# honda_type1.net
KiCad netlist of a schematic drawn in EAGLE
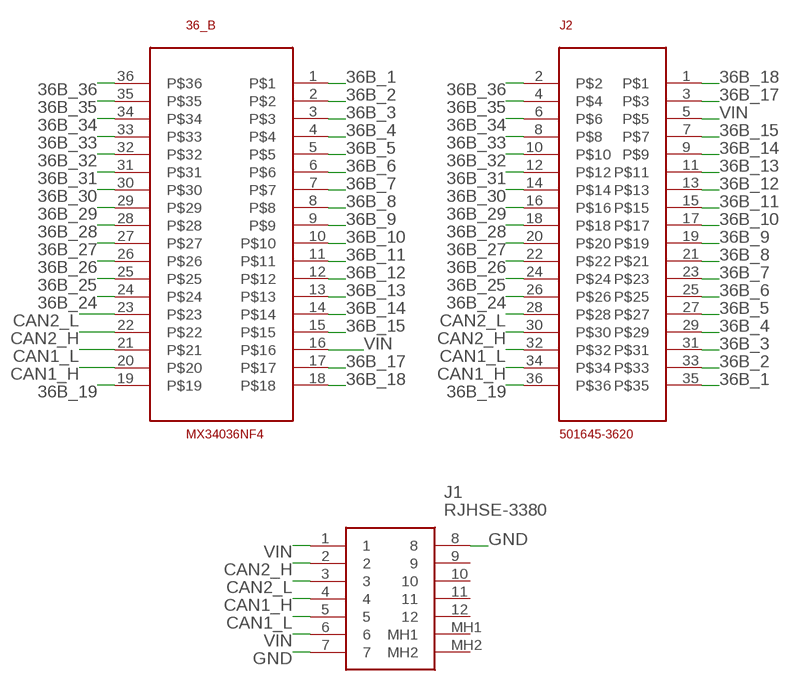
[diagram p0: schematic, sheet 1]

(export (version "E")
  (design (tool "Eeschema 10.0.6"))
  (components
    (comp (ref "36_B")
      (value "MX34036NF4")
      (footprint "eagle-import:MX34036NF2")
      (libsource (lib "eagle-import") (part "MX34036NF4"))
    )
    (comp (ref "J1")
      (value "RJHSE-3380")
      (footprint "eagle-import:RJHSE3384")
      (fields (field (name "MOUSER2_PART_NUMBER") "523-RJHSE-3380"))
      (libsource (lib "eagle-import") (part "RJHSE-3380"))
    )
    (comp (ref "J2")
      (value "501645-3620")
      (footprint "eagle-import:501645-3620")
      (libsource (lib "eagle-import") (part "501645-3620"))
    )
  )
  (nets
    (net (code "1") (name "36B_1") (class "Default")
      (node (ref "36_B") (pin "1") (pinfunction "P$1_1") (pintype "bidirectional"))
      (node (ref "J2") (pin "35") (pinfunction "P$35_35") (pintype "bidirectional"))
    )
    (net (code "2") (name "36B_2") (class "Default")
      (node (ref "36_B") (pin "2") (pinfunction "P$2_2") (pintype "bidirectional"))
      (node (ref "J2") (pin "33") (pinfunction "P$33_33") (pintype "bidirectional"))
    )
    (net (code "3") (name "36B_3") (class "Default")
      (node (ref "36_B") (pin "3") (pinfunction "P$3_3") (pintype "bidirectional"))
      (node (ref "J2") (pin "31") (pinfunction "P$31_31") (pintype "bidirectional"))
    )
    (net (code "4") (name "36B_4") (class "Default")
      (node (ref "36_B") (pin "4") (pinfunction "P$4_4") (pintype "bidirectional"))
      (node (ref "J2") (pin "29") (pinfunction "P$29_29") (pintype "bidirectional"))
    )
    (net (code "5") (name "36B_5") (class "Default")
      (node (ref "36_B") (pin "5") (pinfunction "P$5_5") (pintype "bidirectional"))
      (node (ref "J2") (pin "27") (pinfunction "P$27_27") (pintype "bidirectional"))
    )
    (net (code "6") (name "36B_6") (class "Default")
      (node (ref "36_B") (pin "6") (pinfunction "P$6_6") (pintype "bidirectional"))
      (node (ref "J2") (pin "25") (pinfunction "P$25_25") (pintype "bidirectional"))
    )
    (net (code "7") (name "36B_7") (class "Default")
      (node (ref "36_B") (pin "7") (pinfunction "P$7_7") (pintype "bidirectional"))
      (node (ref "J2") (pin "23") (pinfunction "P$23_23") (pintype "bidirectional"))
    )
    (net (code "8") (name "36B_8") (class "Default")
      (node (ref "36_B") (pin "8") (pinfunction "P$8_8") (pintype "bidirectional"))
      (node (ref "J2") (pin "21") (pinfunction "P$21_21") (pintype "bidirectional"))
    )
    (net (code "9") (name "36B_9") (class "Default")
      (node (ref "36_B") (pin "9") (pinfunction "P$9_9") (pintype "bidirectional"))
      (node (ref "J2") (pin "19") (pinfunction "P$19_19") (pintype "bidirectional"))
    )
    (net (code "10") (name "36B_10") (class "Default")
      (node (ref "36_B") (pin "10") (pinfunction "P$10_10") (pintype "bidirectional"))
      (node (ref "J2") (pin "17") (pinfunction "P$17_17") (pintype "bidirectional"))
    )
    (net (code "11") (name "36B_11") (class "Default")
      (node (ref "36_B") (pin "11") (pinfunction "P$11_11") (pintype "bidirectional"))
      (node (ref "J2") (pin "15") (pinfunction "P$15_15") (pintype "bidirectional"))
    )
    (net (code "12") (name "36B_12") (class "Default")
      (node (ref "36_B") (pin "12") (pinfunction "P$12_12") (pintype "bidirectional"))
      (node (ref "J2") (pin "13") (pinfunction "P$13_13") (pintype "bidirectional"))
    )
    (net (code "13") (name "36B_13") (class "Default")
      (node (ref "36_B") (pin "13") (pinfunction "P$13_13") (pintype "bidirectional"))
      (node (ref "J2") (pin "11") (pinfunction "P$11_11") (pintype "bidirectional"))
    )
    (net (code "14") (name "36B_14") (class "Default")
      (node (ref "36_B") (pin "14") (pinfunction "P$14_14") (pintype "bidirectional"))
      (node (ref "J2") (pin "9") (pinfunction "P$9_9") (pintype "bidirectional"))
    )
    (net (code "15") (name "36B_15") (class "Default")
      (node (ref "36_B") (pin "15") (pinfunction "P$15_15") (pintype "bidirectional"))
      (node (ref "J2") (pin "7") (pinfunction "P$7_7") (pintype "bidirectional"))
    )
    (net (code "16") (name "36B_17") (class "Default")
      (node (ref "36_B") (pin "17") (pinfunction "P$17_17") (pintype "bidirectional"))
      (node (ref "J2") (pin "3") (pinfunction "P$3_3") (pintype "bidirectional"))
    )
    (net (code "17") (name "36B_18") (class "Default")
      (node (ref "36_B") (pin "18") (pinfunction "P$18_18") (pintype "bidirectional"))
      (node (ref "J2") (pin "1") (pinfunction "P$1_1") (pintype "bidirectional"))
    )
    (net (code "18") (name "36B_19") (class "Default")
      (node (ref "36_B") (pin "19") (pinfunction "P$19_19") (pintype "bidirectional"))
      (node (ref "J2") (pin "36") (pinfunction "P$36_36") (pintype "bidirectional"))
    )
    (net (code "19") (name "36B_24") (class "Default")
      (node (ref "36_B") (pin "24") (pinfunction "P$24_24") (pintype "bidirectional"))
      (node (ref "J2") (pin "26") (pinfunction "P$26_26") (pintype "bidirectional"))
    )
    (net (code "20") (name "36B_25") (class "Default")
      (node (ref "36_B") (pin "25") (pinfunction "P$25_25") (pintype "bidirectional"))
      (node (ref "J2") (pin "24") (pinfunction "P$24_24") (pintype "bidirectional"))
    )
    (net (code "21") (name "36B_26") (class "Default")
      (node (ref "36_B") (pin "26") (pinfunction "P$26_26") (pintype "bidirectional"))
      (node (ref "J2") (pin "22") (pinfunction "P$22_22") (pintype "bidirectional"))
    )
    (net (code "22") (name "36B_27") (class "Default")
      (node (ref "36_B") (pin "27") (pinfunction "P$27_27") (pintype "bidirectional"))
      (node (ref "J2") (pin "20") (pinfunction "P$20_20") (pintype "bidirectional"))
    )
    (net (code "23") (name "36B_28") (class "Default")
      (node (ref "36_B") (pin "28") (pinfunction "P$28_28") (pintype "bidirectional"))
      (node (ref "J2") (pin "18") (pinfunction "P$18_18") (pintype "bidirectional"))
    )
    (net (code "24") (name "36B_29") (class "Default")
      (node (ref "36_B") (pin "29") (pinfunction "P$29_29") (pintype "bidirectional"))
      (node (ref "J2") (pin "16") (pinfunction "P$16_16") (pintype "bidirectional"))
    )
    (net (code "25") (name "36B_30") (class "Default")
      (node (ref "36_B") (pin "30") (pinfunction "P$30_30") (pintype "bidirectional"))
      (node (ref "J2") (pin "14") (pinfunction "P$14_14") (pintype "bidirectional"))
    )
    (net (code "26") (name "36B_31") (class "Default")
      (node (ref "36_B") (pin "31") (pinfunction "P$31_31") (pintype "bidirectional"))
      (node (ref "J2") (pin "12") (pinfunction "P$12_12") (pintype "bidirectional"))
    )
    (net (code "27") (name "36B_32") (class "Default")
      (node (ref "36_B") (pin "32") (pinfunction "P$32_32") (pintype "bidirectional"))
      (node (ref "J2") (pin "10") (pinfunction "P$10_10") (pintype "bidirectional"))
    )
    (net (code "28") (name "36B_33") (class "Default")
      (node (ref "36_B") (pin "33") (pinfunction "P$33_33") (pintype "bidirectional"))
      (node (ref "J2") (pin "8") (pinfunction "P$8_8") (pintype "bidirectional"))
    )
    (net (code "29") (name "36B_34") (class "Default")
      (node (ref "36_B") (pin "34") (pinfunction "P$34_34") (pintype "bidirectional"))
      (node (ref "J2") (pin "6") (pinfunction "P$6_6") (pintype "bidirectional"))
    )
    (net (code "30") (name "36B_35") (class "Default")
      (node (ref "36_B") (pin "35") (pinfunction "P$35_35") (pintype "bidirectional"))
      (node (ref "J2") (pin "4") (pinfunction "P$4_4") (pintype "bidirectional"))
    )
    (net (code "31") (name "36B_36") (class "Default")
      (node (ref "36_B") (pin "36") (pinfunction "P$36_36") (pintype "bidirectional"))
      (node (ref "J2") (pin "2") (pinfunction "P$2_2") (pintype "bidirectional"))
    )
    (net (code "32") (name "CAN1_H") (class "Default")
      (node (ref "36_B") (pin "20") (pinfunction "P$20_20") (pintype "bidirectional"))
      (node (ref "J1") (pin "4") (pinfunction "4_4") (pintype "bidirectional"))
      (node (ref "J2") (pin "34") (pinfunction "P$34_34") (pintype "bidirectional"))
    )
    (net (code "33") (name "CAN1_L") (class "Default")
      (node (ref "36_B") (pin "21") (pinfunction "P$21_21") (pintype "bidirectional"))
      (node (ref "J1") (pin "5") (pinfunction "5_5") (pintype "bidirectional"))
      (node (ref "J2") (pin "32") (pinfunction "P$32_32") (pintype "bidirectional"))
    )
    (net (code "34") (name "CAN2_H") (class "Default")
      (node (ref "36_B") (pin "22") (pinfunction "P$22_22") (pintype "bidirectional"))
      (node (ref "J1") (pin "2") (pinfunction "2_2") (pintype "bidirectional"))
      (node (ref "J2") (pin "30") (pinfunction "P$30_30") (pintype "bidirectional"))
    )
    (net (code "35") (name "CAN2_L") (class "Default")
      (node (ref "36_B") (pin "23") (pinfunction "P$23_23") (pintype "bidirectional"))
      (node (ref "J1") (pin "3") (pinfunction "3_3") (pintype "bidirectional"))
      (node (ref "J2") (pin "28") (pinfunction "P$28_28") (pintype "bidirectional"))
    )
    (net (code "36") (name "GND") (class "Default")
      (node (ref "J1") (pin "7") (pinfunction "7_7") (pintype "bidirectional"))
      (node (ref "J1") (pin "8") (pinfunction "8_8") (pintype "bidirectional"))
    )
    (net (code "37") (name "VIN") (class "Default")
      (node (ref "36_B") (pin "16") (pinfunction "P$16_16") (pintype "bidirectional"))
      (node (ref "J1") (pin "1") (pinfunction "1_1") (pintype "bidirectional"))
      (node (ref "J1") (pin "6") (pinfunction "6_6") (pintype "bidirectional"))
      (node (ref "J2") (pin "5") (pinfunction "P$5_5") (pintype "bidirectional"))
    )
    (net (code "38") (name "unconnected-(J1-Pad9)") (class "Default")
      (node (ref "J1") (pin "9") (pinfunction "9_9") (pintype "bidirectional"))
    )
    (net (code "39") (name "unconnected-(J1-Pad10)") (class "Default")
      (node (ref "J1") (pin "10") (pinfunction "10_10") (pintype "bidirectional"))
    )
    (net (code "40") (name "unconnected-(J1-Pad11)") (class "Default")
      (node (ref "J1") (pin "11") (pinfunction "11_11") (pintype "bidirectional"))
    )
    (net (code "41") (name "unconnected-(J1-Pad12)") (class "Default")
      (node (ref "J1") (pin "12") (pinfunction "12_12") (pintype "bidirectional"))
    )
    (net (code "42") (name "unconnected-(J1-PadMH1)") (class "Default")
      (node (ref "J1") (pin "MH1") (pinfunction "MH1_MH1") (pintype "bidirectional"))
    )
    (net (code "43") (name "unconnected-(J1-PadMH2)") (class "Default")
      (node (ref "J1") (pin "MH2") (pinfunction "MH2_MH2") (pintype "bidirectional"))
    )
  )
)
